# attinier85-motherboard-mk-3_1.net
KiCad netlist of a schematic drawn in EAGLE
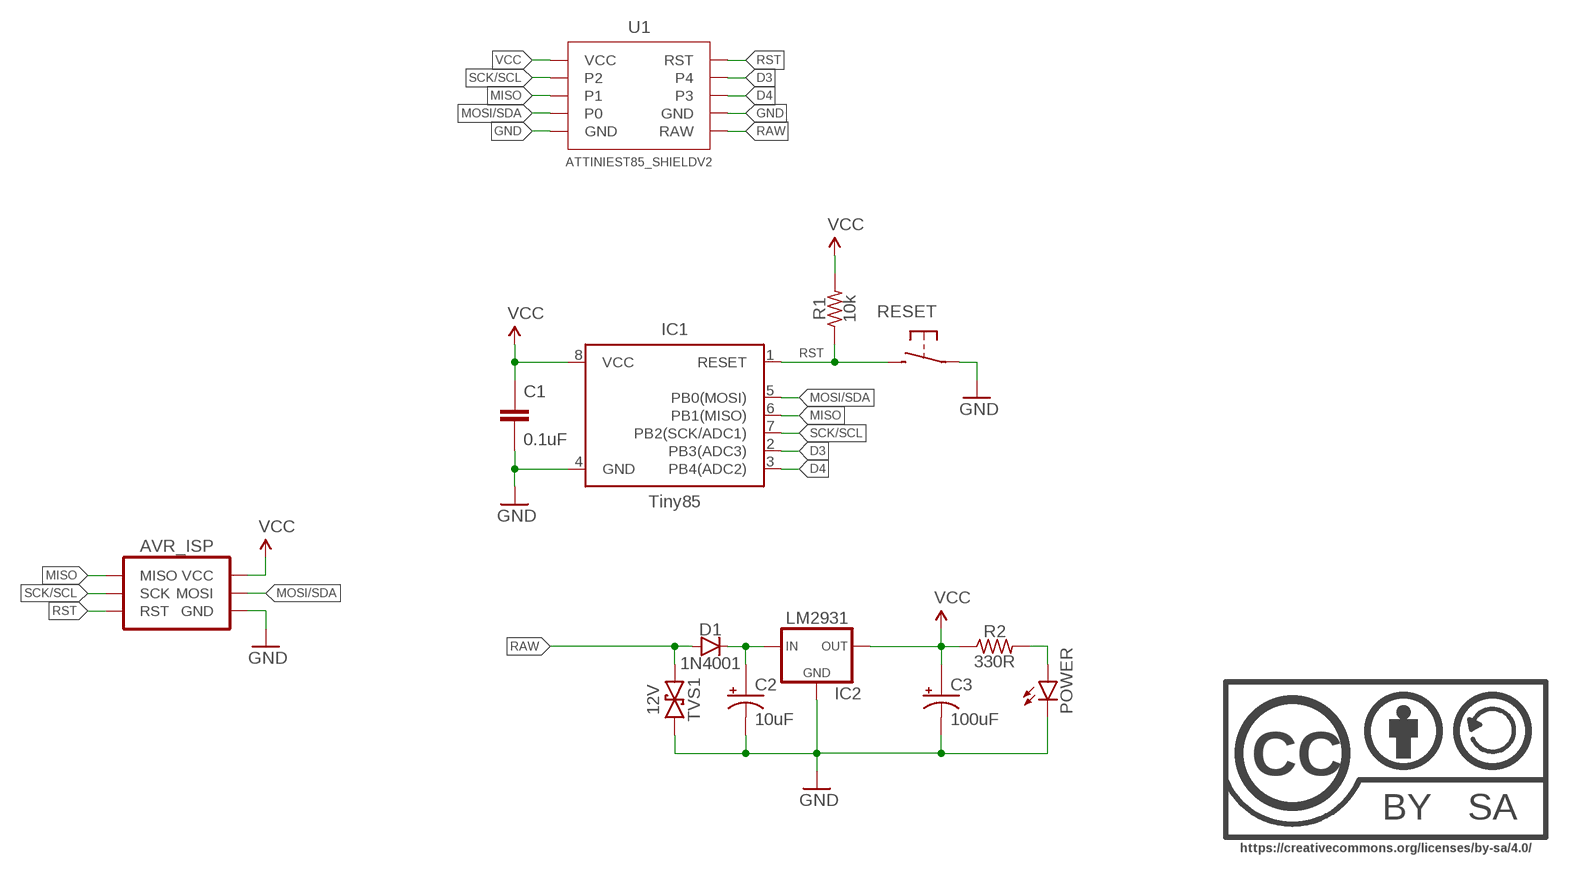
[diagram p0: schematic, sheet 1]

(export (version "E")
  (design (tool "Eeschema 10.0.6"))
  (components
    (comp (ref "AVR_ISP")
      (value "AVR_SPI_PRG_6PTH")
      (footprint "eagle-import:2X3")
      (libsource (lib "eagle-import") (part "AVR_SPI_PRG_6PTH"))
    )
    (comp (ref "C1")
      (value "0.1uF")
      (footprint "eagle-import:C025-024X044")
      (libsource (lib "eagle-import") (part "CAPACITOR-CERAMIC025-024X044"))
    )
    (comp (ref "C2")
      (value "10uF")
      (footprint "eagle-import:E2,5-5")
      (libsource (lib "eagle-import") (part "CAPACITOR-POLARIZEDE2.5-5"))
    )
    (comp (ref "C3")
      (value "100uF")
      (footprint "eagle-import:E2,5-5")
      (libsource (lib "eagle-import") (part "CAPACITOR-POLARIZEDE2.5-5"))
    )
    (comp (ref "D1")
      (value "1N4001")
      (footprint "eagle-import:DIODE-10.16MM")
      (libsource (lib "eagle-import") (part "DIODEPTH-10.68MM"))
    )
    (comp (ref "IC1")
      (value "Tiny85")
      (footprint "eagle-import:DIP08")
      (libsource (lib "eagle-import") (part "ATTINY45TINY85-20-DIP"))
    )
    (comp (ref "IC2")
      (value "LM2931")
      (footprint "eagle-import:TO-92-AMMO")
      (libsource (lib "eagle-import") (part "V_REG_78XXTO-92-INLINE"))
    )
    (comp (ref "POWER")
      (value "LED3MM-LESS")
      (footprint "eagle-import:LED3MM-LESSSILK")
      (libsource (lib "eagle-import") (part "LED3MM-LESS"))
    )
    (comp (ref "R1")
      (value "10k")
      (footprint "eagle-import:RESISTOR-AXIAL-PTH-7.62MM")
      (libsource (lib "eagle-import") (part "RESISTORPTH-AXIAL-7.62MM"))
    )
    (comp (ref "R2")
      (value "330R")
      (footprint "eagle-import:RESISTOR-AXIAL-PTH-7.62MM")
      (libsource (lib "eagle-import") (part "RESISTORPTH-AXIAL-7.62MM"))
    )
    (comp (ref "RESET")
      (value "DTS-6MM")
      (footprint "eagle-import:DTS-3-SMALL-PADS")
      (libsource (lib "eagle-import") (part "SPST-NO-TACT3MM-PTH-SMALL-PADS"))
    )
    (comp (ref "TVS1")
      (value "12V")
      (footprint "eagle-import:DO-41-TVS")
      (libsource (lib "eagle-import") (part "TVSDO-41-TVS-BIDIRECTIONAL"))
    )
    (comp (ref "U$1")
      (value "CC-BY-SA-4.0NO-URL")
      (footprint "eagle-import:CC-BY-SA-4.0-NO-URL")
      (libsource (lib "eagle-import") (part "CC-BY-SA-4.0NO-URL"))
    )
    (comp (ref "U1")
      (value "ATTINIEST85_SHIELDV2")
      (footprint "eagle-import:ATTINIEST85_SHIELD_V2")
      (libsource (lib "eagle-import") (part "ATTINIEST85_SHIELDV2"))
    )
  )
  (nets
    (net (code "1") (name "D3") (class "Default")
      (node (ref "IC1") (pin "2") (pinfunction "PB3(ADC3)_2") (pintype "bidirectional"))
      (node (ref "U1") (pin "4") (pinfunction "P4_4") (pintype "bidirectional"))
    )
    (net (code "2") (name "D4") (class "Default")
      (node (ref "IC1") (pin "3") (pinfunction "PB4(ADC2)_3") (pintype "bidirectional"))
      (node (ref "U1") (pin "3") (pinfunction "P3_3") (pintype "bidirectional"))
    )
    (net (code "3") (name "GND") (class "Default")
      (node (ref "AVR_ISP") (pin "6") (pinfunction "GND_6") (pintype "passive"))
      (node (ref "C1") (pin "2") (pinfunction "2_2") (pintype "passive"))
      (node (ref "C2") (pin "-") (pinfunction "-_-") (pintype "passive"))
      (node (ref "C3") (pin "-") (pinfunction "-_-") (pintype "passive"))
      (node (ref "IC1") (pin "4") (pinfunction "GND_4") (pintype "bidirectional"))
      (node (ref "IC2") (pin "2") (pinfunction "GND_2") (pintype "bidirectional"))
      (node (ref "POWER") (pin "K") (pinfunction "C_K") (pintype "passive"))
      (node (ref "RESET") (pin "1") (pinfunction "1_1") (pintype "passive"))
      (node (ref "TVS1") (pin "P$2") (pinfunction "2_P$2") (pintype "passive"))
      (node (ref "U1") (pin "GND@1") (pinfunction "GND_GND@1") (pintype "bidirectional"))
      (node (ref "U1") (pin "GND@2") (pinfunction "GND_GND@2") (pintype "bidirectional"))
    )
    (net (code "4") (name "MISO") (class "Default")
      (node (ref "AVR_ISP") (pin "1") (pinfunction "MISO_1") (pintype "passive"))
      (node (ref "IC1") (pin "6") (pinfunction "PB1(MISO)_6") (pintype "bidirectional"))
      (node (ref "U1") (pin "1") (pinfunction "P1_1") (pintype "bidirectional"))
    )
    (net (code "5") (name "MOSI{slash}SDA") (class "Default")
      (node (ref "AVR_ISP") (pin "4") (pinfunction "MOSI_4") (pintype "passive"))
      (node (ref "IC1") (pin "5") (pinfunction "PB0(MOSI)_5") (pintype "bidirectional"))
      (node (ref "U1") (pin "0") (pinfunction "P0_0") (pintype "bidirectional"))
    )
    (net (code "6") (name "Net-(IC2-IN)") (class "Default")
      (node (ref "C2") (pin "+") (pinfunction "+_+") (pintype "passive"))
      (node (ref "D1") (pin "C") (pinfunction "C_C") (pintype "passive"))
      (node (ref "IC2") (pin "1") (pinfunction "IN_1") (pintype "bidirectional"))
    )
    (net (code "7") (name "Net-(R2-2)") (class "Default")
      (node (ref "POWER") (pin "A") (pinfunction "A_A") (pintype "passive"))
      (node (ref "R2") (pin "P$2") (pinfunction "2_P$2") (pintype "passive"))
    )
    (net (code "8") (name "RAW") (class "Default")
      (node (ref "D1") (pin "A") (pinfunction "A_A") (pintype "passive"))
      (node (ref "TVS1") (pin "P$1") (pinfunction "1_P$1") (pintype "passive"))
      (node (ref "U1") (pin "RAW") (pinfunction "RAW_RAW") (pintype "bidirectional"))
    )
    (net (code "9") (name "RST") (class "Default")
      (node (ref "AVR_ISP") (pin "5") (pinfunction "RST_5") (pintype "passive"))
      (node (ref "IC1") (pin "1") (pinfunction "RESET_1") (pintype "bidirectional"))
      (node (ref "R1") (pin "P$1") (pinfunction "1_P$1") (pintype "passive"))
      (node (ref "RESET") (pin "2") (pinfunction "2_2") (pintype "passive"))
      (node (ref "U1") (pin "RST") (pinfunction "RST_RST") (pintype "bidirectional"))
    )
    (net (code "10") (name "SCK{slash}SCL") (class "Default")
      (node (ref "AVR_ISP") (pin "3") (pinfunction "SCK_3") (pintype "passive"))
      (node (ref "IC1") (pin "7") (pinfunction "PB2(SCK/ADC1)_7") (pintype "bidirectional"))
      (node (ref "U1") (pin "2") (pinfunction "P2_2") (pintype "bidirectional"))
    )
    (net (code "11") (name "VCC") (class "Default")
      (node (ref "AVR_ISP") (pin "2") (pinfunction "VCC_2") (pintype "passive"))
      (node (ref "C1") (pin "1") (pinfunction "1_1") (pintype "passive"))
      (node (ref "C3") (pin "+") (pinfunction "+_+") (pintype "passive"))
      (node (ref "IC1") (pin "8") (pinfunction "VCC_8") (pintype "bidirectional"))
      (node (ref "IC2") (pin "3") (pinfunction "OUT_3") (pintype "bidirectional"))
      (node (ref "R1") (pin "P$2") (pinfunction "2_P$2") (pintype "passive"))
      (node (ref "R2") (pin "P$1") (pinfunction "1_P$1") (pintype "passive"))
      (node (ref "U1") (pin "VCC") (pinfunction "VCC_VCC") (pintype "bidirectional"))
    )
  )
)
